# Display_Board_V1.net
KiCad netlist of a schematic drawn in EAGLE
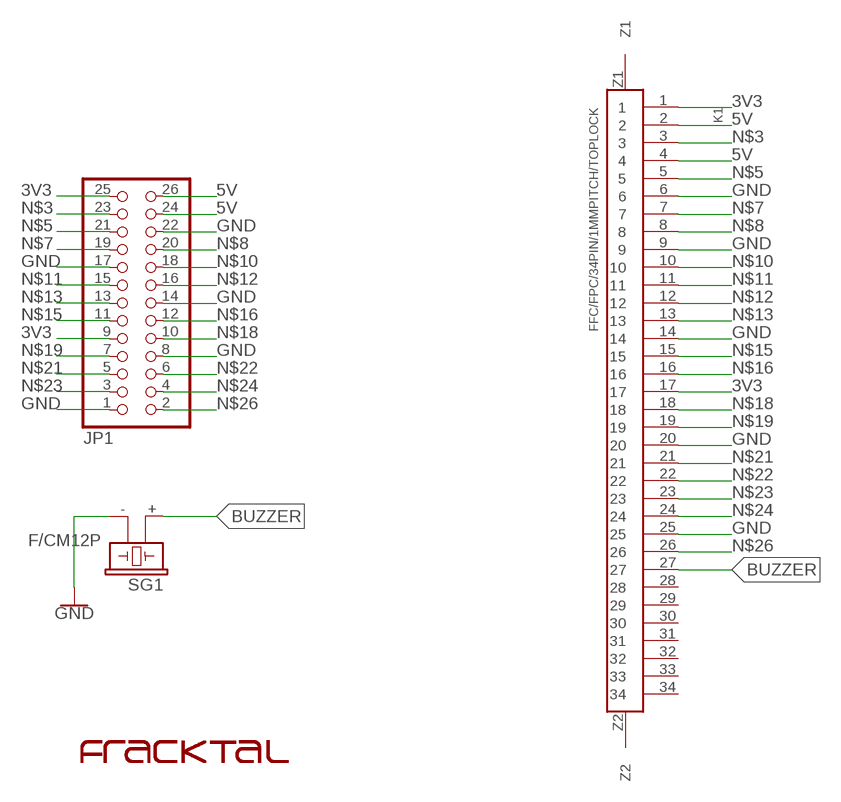
[diagram p0: schematic, sheet 1]

(export (version "E")
  (design (tool "Eeschema 10.0.6"))
  (components
    (comp (ref "JP1")
      (value "PINHD-2X13")
      (footprint "eagle-import:2X13")
      (libsource (lib "eagle-import") (part "PINHD-2X13"))
    )
    (comp (ref "K1")
      (value "FFC/FPC/34PIN/1MMPITCH/TOPLOCK")
      (footprint "eagle-import:FFC_FPC_34PIN_1MMPITCH_TOPLOCK")
      (libsource (lib "eagle-import") (part "FFC/FPC/34PIN/1MMPITCH/TOPLOCK"))
    )
    (comp (ref "SG1")
      (value "F/CM12P")
      (footprint "eagle-import:F_CM12P")
      (libsource (lib "eagle-import") (part "F/CM12P"))
    )
    (comp (ref "U$1")
      (value "FRACKTALLOGO")
      (footprint "eagle-import:FRACKTALLOGO")
      (libsource (lib "eagle-import") (part "FRACKTALLOGO"))
    )
  )
  (nets
    (net (code "1") (name "/3V3") (class "Default")
      (node (ref "JP1") (pin "25") (pinfunction "25_25") (pintype "passive"))
      (node (ref "JP1") (pin "9") (pinfunction "9_9") (pintype "passive"))
      (node (ref "K1") (pin "1") (pinfunction "1_1") (pintype "bidirectional"))
      (node (ref "K1") (pin "17") (pinfunction "17_17") (pintype "bidirectional"))
    )
    (net (code "2") (name "/5V") (class "Default")
      (node (ref "JP1") (pin "24") (pinfunction "24_24") (pintype "passive"))
      (node (ref "JP1") (pin "26") (pinfunction "26_26") (pintype "passive"))
      (node (ref "K1") (pin "2") (pinfunction "2_2") (pintype "bidirectional"))
      (node (ref "K1") (pin "4") (pinfunction "4_4") (pintype "bidirectional"))
    )
    (net (code "3") (name "/N$3") (class "Default")
      (node (ref "JP1") (pin "23") (pinfunction "23_23") (pintype "passive"))
      (node (ref "K1") (pin "3") (pinfunction "3_3") (pintype "bidirectional"))
    )
    (net (code "4") (name "/N$5") (class "Default")
      (node (ref "JP1") (pin "21") (pinfunction "21_21") (pintype "passive"))
      (node (ref "K1") (pin "5") (pinfunction "5_5") (pintype "bidirectional"))
    )
    (net (code "5") (name "/N$7") (class "Default")
      (node (ref "JP1") (pin "19") (pinfunction "19_19") (pintype "passive"))
      (node (ref "K1") (pin "7") (pinfunction "7_7") (pintype "bidirectional"))
    )
    (net (code "6") (name "/N$8") (class "Default")
      (node (ref "JP1") (pin "20") (pinfunction "20_20") (pintype "passive"))
      (node (ref "K1") (pin "8") (pinfunction "8_8") (pintype "bidirectional"))
    )
    (net (code "7") (name "/N$10") (class "Default")
      (node (ref "JP1") (pin "18") (pinfunction "18_18") (pintype "passive"))
      (node (ref "K1") (pin "10") (pinfunction "10_10") (pintype "bidirectional"))
    )
    (net (code "8") (name "/N$11") (class "Default")
      (node (ref "JP1") (pin "15") (pinfunction "15_15") (pintype "passive"))
      (node (ref "K1") (pin "11") (pinfunction "11_11") (pintype "bidirectional"))
    )
    (net (code "9") (name "/N$12") (class "Default")
      (node (ref "JP1") (pin "16") (pinfunction "16_16") (pintype "passive"))
      (node (ref "K1") (pin "12") (pinfunction "12_12") (pintype "bidirectional"))
    )
    (net (code "10") (name "/N$13") (class "Default")
      (node (ref "JP1") (pin "13") (pinfunction "13_13") (pintype "passive"))
      (node (ref "K1") (pin "13") (pinfunction "13_13") (pintype "bidirectional"))
    )
    (net (code "11") (name "/N$15") (class "Default")
      (node (ref "JP1") (pin "11") (pinfunction "11_11") (pintype "passive"))
      (node (ref "K1") (pin "15") (pinfunction "15_15") (pintype "bidirectional"))
    )
    (net (code "12") (name "/N$16") (class "Default")
      (node (ref "JP1") (pin "12") (pinfunction "12_12") (pintype "passive"))
      (node (ref "K1") (pin "16") (pinfunction "16_16") (pintype "bidirectional"))
    )
    (net (code "13") (name "/N$18") (class "Default")
      (node (ref "JP1") (pin "10") (pinfunction "10_10") (pintype "passive"))
      (node (ref "K1") (pin "18") (pinfunction "18_18") (pintype "bidirectional"))
    )
    (net (code "14") (name "/N$19") (class "Default")
      (node (ref "JP1") (pin "7") (pinfunction "7_7") (pintype "passive"))
      (node (ref "K1") (pin "19") (pinfunction "19_19") (pintype "bidirectional"))
    )
    (net (code "15") (name "/N$21") (class "Default")
      (node (ref "JP1") (pin "5") (pinfunction "5_5") (pintype "passive"))
      (node (ref "K1") (pin "21") (pinfunction "21_21") (pintype "bidirectional"))
    )
    (net (code "16") (name "/N$22") (class "Default")
      (node (ref "JP1") (pin "6") (pinfunction "6_6") (pintype "passive"))
      (node (ref "K1") (pin "22") (pinfunction "22_22") (pintype "bidirectional"))
    )
    (net (code "17") (name "/N$23") (class "Default")
      (node (ref "JP1") (pin "3") (pinfunction "3_3") (pintype "passive"))
      (node (ref "K1") (pin "23") (pinfunction "23_23") (pintype "bidirectional"))
    )
    (net (code "18") (name "/N$24") (class "Default")
      (node (ref "JP1") (pin "4") (pinfunction "4_4") (pintype "passive"))
      (node (ref "K1") (pin "24") (pinfunction "24_24") (pintype "bidirectional"))
    )
    (net (code "19") (name "/N$26") (class "Default")
      (node (ref "JP1") (pin "2") (pinfunction "2_2") (pintype "passive"))
      (node (ref "K1") (pin "26") (pinfunction "26_26") (pintype "bidirectional"))
    )
    (net (code "20") (name "BUZZER") (class "Default")
      (node (ref "K1") (pin "27") (pinfunction "27_27") (pintype "bidirectional"))
      (node (ref "SG1") (pin "+") (pinfunction "1_+") (pintype "passive"))
    )
    (net (code "21") (name "GND") (class "Default")
      (node (ref "JP1") (pin "1") (pinfunction "1_1") (pintype "passive"))
      (node (ref "JP1") (pin "14") (pinfunction "14_14") (pintype "passive"))
      (node (ref "JP1") (pin "17") (pinfunction "17_17") (pintype "passive"))
      (node (ref "JP1") (pin "22") (pinfunction "22_22") (pintype "passive"))
      (node (ref "JP1") (pin "8") (pinfunction "8_8") (pintype "passive"))
      (node (ref "K1") (pin "14") (pinfunction "14_14") (pintype "bidirectional"))
      (node (ref "K1") (pin "20") (pinfunction "20_20") (pintype "bidirectional"))
      (node (ref "K1") (pin "25") (pinfunction "25_25") (pintype "bidirectional"))
      (node (ref "K1") (pin "6") (pinfunction "6_6") (pintype "bidirectional"))
      (node (ref "K1") (pin "9") (pinfunction "9_9") (pintype "bidirectional"))
      (node (ref "SG1") (pin "-") (pinfunction "2_-") (pintype "passive"))
    )
    (net (code "22") (name "unconnected-(K1-Pad28)") (class "Default")
      (node (ref "K1") (pin "28") (pinfunction "28_28") (pintype "bidirectional"))
    )
    (net (code "23") (name "unconnected-(K1-Pad29)") (class "Default")
      (node (ref "K1") (pin "29") (pinfunction "29_29") (pintype "bidirectional"))
    )
    (net (code "24") (name "unconnected-(K1-Pad30)") (class "Default")
      (node (ref "K1") (pin "30") (pinfunction "30_30") (pintype "bidirectional"))
    )
    (net (code "25") (name "unconnected-(K1-Pad31)") (class "Default")
      (node (ref "K1") (pin "31") (pinfunction "31_31") (pintype "bidirectional"))
    )
    (net (code "26") (name "unconnected-(K1-Pad32)") (class "Default")
      (node (ref "K1") (pin "32") (pinfunction "32_32") (pintype "bidirectional"))
    )
    (net (code "27") (name "unconnected-(K1-Pad33)") (class "Default")
      (node (ref "K1") (pin "33") (pinfunction "33_33") (pintype "bidirectional"))
    )
    (net (code "28") (name "unconnected-(K1-Pad34)") (class "Default")
      (node (ref "K1") (pin "34") (pinfunction "34_34") (pintype "bidirectional"))
    )
    (net (code "29") (name "unconnected-(K1-PadZ1)") (class "Default")
      (node (ref "K1") (pin "Z1") (pinfunction "Z1_Z1") (pintype "bidirectional"))
    )
    (net (code "30") (name "unconnected-(K1-PadZ2)") (class "Default")
      (node (ref "K1") (pin "Z2") (pinfunction "Z2_Z2") (pintype "bidirectional"))
    )
  )
)
